# 4_Unextended_Standard_periferals.net
KiCad netlist of a schematic drawn in Altium Designer
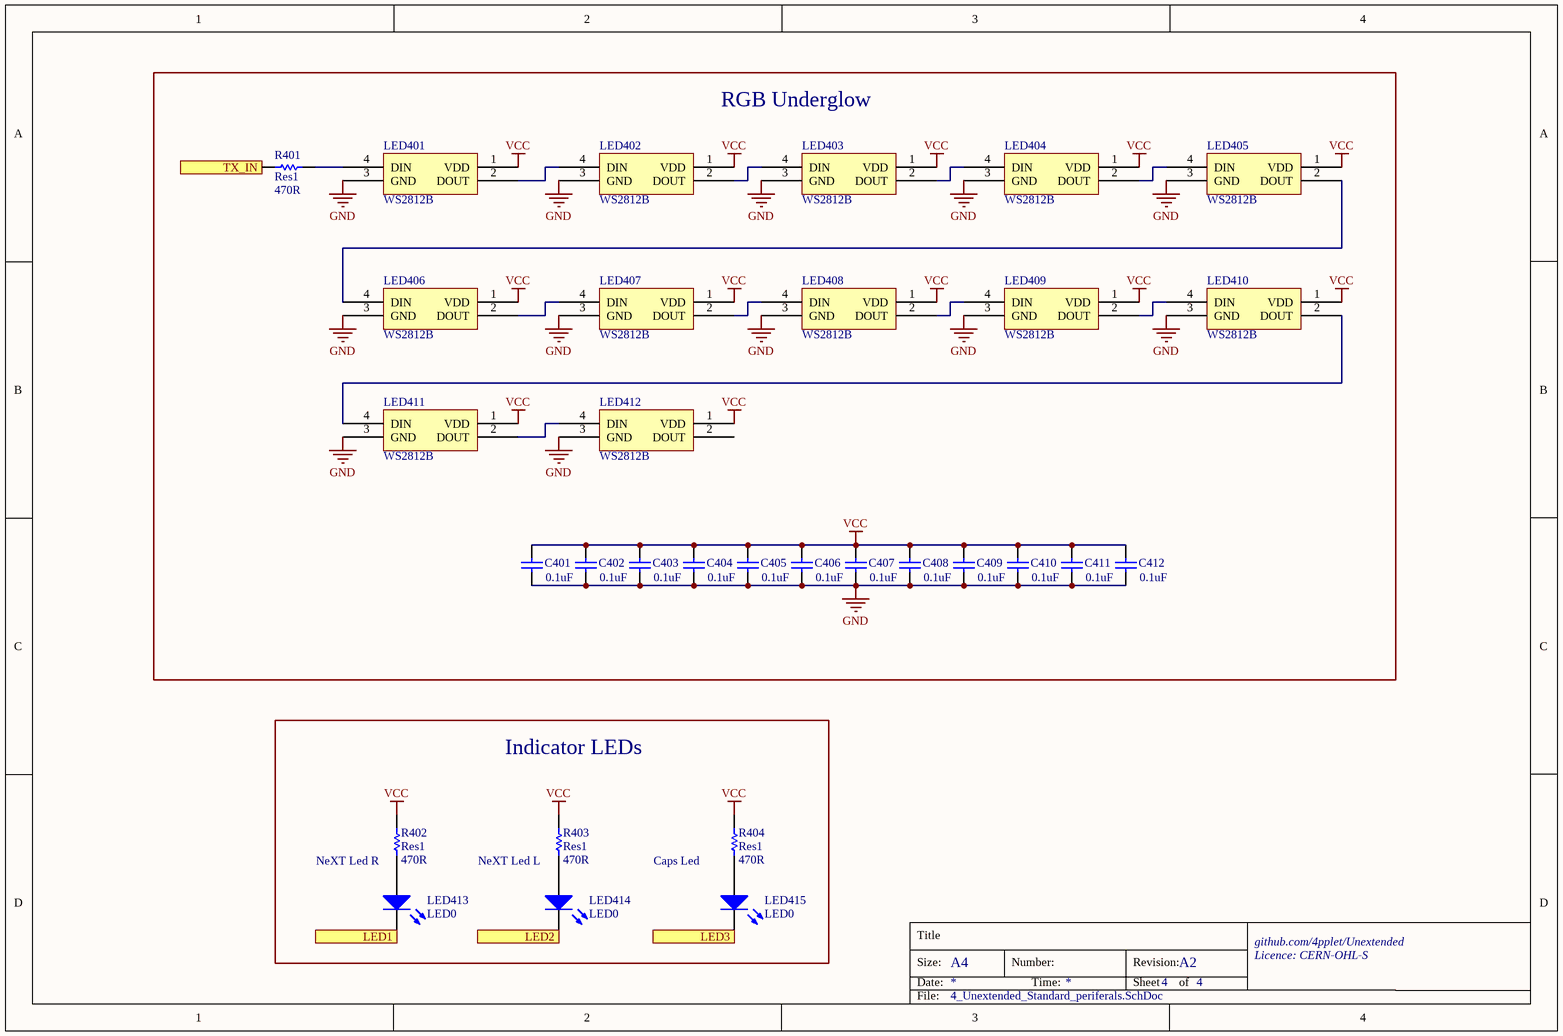
[diagram p0: 4_Unextended_Standard_periferals.SchDoc]

(export (version "E")
  (design (tool "Eeschema 10.0.6"))
  (components
    (comp (ref "C401")
      (value "0.1uF")
      (footprint "C0603[1608]")
      (description "Capacitor")
      (fields (field (name "LCSC PART #") "C14663") (field (name "MRF.PART") "CC0603KRX7R9BB104"))
      (libsource (lib "Miscellaneous Devices") (part "Cap"))
    )
    (comp (ref "C402")
      (value "0.1uF")
      (footprint "C0603[1608]")
      (description "Capacitor")
      (fields (field (name "LCSC PART #") "C14663") (field (name "MRF.PART") "CC0603KRX7R9BB104"))
      (libsource (lib "Miscellaneous Devices") (part "Cap"))
    )
    (comp (ref "C403")
      (value "0.1uF")
      (footprint "C0603[1608]")
      (description "Capacitor")
      (fields (field (name "LCSC PART #") "C14663") (field (name "MRF.PART") "CC0603KRX7R9BB104"))
      (libsource (lib "Miscellaneous Devices") (part "Cap"))
    )
    (comp (ref "C404")
      (value "0.1uF")
      (footprint "C0603[1608]")
      (description "Capacitor")
      (fields (field (name "LCSC PART #") "C14663") (field (name "MRF.PART") "CC0603KRX7R9BB104"))
      (libsource (lib "Miscellaneous Devices") (part "Cap"))
    )
    (comp (ref "C405")
      (value "0.1uF")
      (footprint "C0603[1608]")
      (description "Capacitor")
      (fields (field (name "LCSC PART #") "C14663") (field (name "MRF.PART") "CC0603KRX7R9BB104"))
      (libsource (lib "Miscellaneous Devices") (part "Cap"))
    )
    (comp (ref "C406")
      (value "0.1uF")
      (footprint "C0603[1608]")
      (description "Capacitor")
      (fields (field (name "LCSC PART #") "C14663") (field (name "MRF.PART") "CC0603KRX7R9BB104"))
      (libsource (lib "Miscellaneous Devices") (part "Cap"))
    )
    (comp (ref "C407")
      (value "0.1uF")
      (footprint "C0603[1608]")
      (description "Capacitor")
      (fields (field (name "LCSC PART #") "C14663") (field (name "MRF.PART") "CC0603KRX7R9BB104"))
      (libsource (lib "Miscellaneous Devices") (part "Cap"))
    )
    (comp (ref "C408")
      (value "0.1uF")
      (footprint "C0603[1608]")
      (description "Capacitor")
      (fields (field (name "LCSC PART #") "C14663") (field (name "MRF.PART") "CC0603KRX7R9BB104"))
      (libsource (lib "Miscellaneous Devices") (part "Cap"))
    )
    (comp (ref "C409")
      (value "0.1uF")
      (footprint "C0603[1608]")
      (description "Capacitor")
      (fields (field (name "LCSC PART #") "C14663") (field (name "MRF.PART") "CC0603KRX7R9BB104"))
      (libsource (lib "Miscellaneous Devices") (part "Cap"))
    )
    (comp (ref "C410")
      (value "0.1uF")
      (footprint "C0603[1608]")
      (description "Capacitor")
      (fields (field (name "LCSC PART #") "C14663") (field (name "MRF.PART") "CC0603KRX7R9BB104"))
      (libsource (lib "Miscellaneous Devices") (part "Cap"))
    )
    (comp (ref "C411")
      (value "0.1uF")
      (footprint "C0603[1608]")
      (description "Capacitor")
      (fields (field (name "LCSC PART #") "C14663") (field (name "MRF.PART") "CC0603KRX7R9BB104"))
      (libsource (lib "Miscellaneous Devices") (part "Cap"))
    )
    (comp (ref "C412")
      (value "0.1uF")
      (footprint "C0603[1608]")
      (description "Capacitor")
      (fields (field (name "LCSC PART #") "C14663") (field (name "MRF.PART") "CC0603KRX7R9BB104"))
      (libsource (lib "Miscellaneous Devices") (part "Cap"))
    )
    (comp (ref "LED401")
      (value "WS2812B")
      (footprint "WS2812B - 5050")
      (fields (field (name "LCSC PART #") "C2920042") (field (name "MRF.PART") "WS2812E-V5"))
      (libsource (lib "Keebs") (part "WS2812B"))
    )
    (comp (ref "LED402")
      (value "WS2812B")
      (footprint "WS2812B - 5050")
      (fields (field (name "LCSC PART #") "C2920042") (field (name "MRF.PART") "WS2812E-V5"))
      (libsource (lib "Keebs") (part "WS2812B"))
    )
    (comp (ref "LED403")
      (value "WS2812B")
      (footprint "WS2812B - 5050")
      (fields (field (name "LCSC PART #") "C2920042") (field (name "MRF.PART") "WS2812E-V5"))
      (libsource (lib "Keebs") (part "WS2812B"))
    )
    (comp (ref "LED404")
      (value "WS2812B")
      (footprint "WS2812B - 5050")
      (fields (field (name "LCSC PART #") "C2920042") (field (name "MRF.PART") "WS2812E-V5"))
      (libsource (lib "Keebs") (part "WS2812B"))
    )
    (comp (ref "LED405")
      (value "WS2812B")
      (footprint "WS2812B - 5050")
      (fields (field (name "LCSC PART #") "C2920042") (field (name "MRF.PART") "WS2812E-V5"))
      (libsource (lib "Keebs") (part "WS2812B"))
    )
    (comp (ref "LED406")
      (value "WS2812B")
      (footprint "WS2812B - 5050")
      (fields (field (name "LCSC PART #") "C2920042") (field (name "MRF.PART") "WS2812E-V5"))
      (libsource (lib "Keebs") (part "WS2812B"))
    )
    (comp (ref "LED407")
      (value "WS2812B")
      (footprint "WS2812B - 5050")
      (fields (field (name "LCSC PART #") "C2920042") (field (name "MRF.PART") "WS2812E-V5"))
      (libsource (lib "Keebs") (part "WS2812B"))
    )
    (comp (ref "LED408")
      (value "WS2812B")
      (footprint "WS2812B - 5050")
      (fields (field (name "LCSC PART #") "C2920042") (field (name "MRF.PART") "WS2812E-V5"))
      (libsource (lib "Keebs") (part "WS2812B"))
    )
    (comp (ref "LED409")
      (value "WS2812B")
      (footprint "WS2812B - 5050")
      (fields (field (name "LCSC PART #") "C2920042") (field (name "MRF.PART") "WS2812E-V5"))
      (libsource (lib "Keebs") (part "WS2812B"))
    )
    (comp (ref "LED410")
      (value "WS2812B")
      (footprint "WS2812B - 5050")
      (fields (field (name "LCSC PART #") "C2920042") (field (name "MRF.PART") "WS2812E-V5"))
      (libsource (lib "Keebs") (part "WS2812B"))
    )
    (comp (ref "LED411")
      (value "WS2812B")
      (footprint "WS2812B - 5050")
      (fields (field (name "LCSC PART #") "C2920042") (field (name "MRF.PART") "WS2812E-V5"))
      (libsource (lib "Keebs") (part "WS2812B"))
    )
    (comp (ref "LED412")
      (value "WS2812B")
      (footprint "WS2812B - 5050")
      (fields (field (name "LCSC PART #") "C2920042") (field (name "MRF.PART") "WS2812E-V5"))
      (libsource (lib "Keebs") (part "WS2812B"))
    )
    (comp (ref "LED413")
      (value "LED0")
      (footprint "SWITCH_LED - 1U")
      (description "Typical INFRARED GaAs LED")
      (libsource (lib "Miscellaneous Devices") (part "LED0"))
    )
    (comp (ref "LED414")
      (value "LED0")
      (footprint "SWITCH_LED - 1U")
      (description "Typical INFRARED GaAs LED")
      (libsource (lib "Miscellaneous Devices") (part "LED0"))
    )
    (comp (ref "LED415")
      (value "LED0")
      (footprint "SWITCH_LED - 1U")
      (description "Typical INFRARED GaAs LED")
      (libsource (lib "Miscellaneous Devices") (part "LED0"))
    )
    (comp (ref "R401")
      (value "Res1")
      (footprint "R0603[1608]")
      (description "Resistor")
      (fields
        (field (name "ALTIUM_VALUE") "470R")
        (field (name "LCSC PART #") "C23179")
        (field (name "MRF.PART") "0603WAF4700T5E")
      )
      (libsource (lib "Miscellaneous Devices") (part "Res1"))
    )
    (comp (ref "R402")
      (value "Res1")
      (footprint "R0603[1608]")
      (description "Resistor")
      (fields
        (field (name "ALTIUM_VALUE") "470R")
        (field (name "LCSC PART #") "C23179")
        (field (name "MRF.PART") "0603WAF4700T5E")
      )
      (libsource (lib "Miscellaneous Devices") (part "Res1"))
    )
    (comp (ref "R403")
      (value "Res1")
      (footprint "R0603[1608]")
      (description "Resistor")
      (fields
        (field (name "ALTIUM_VALUE") "470R")
        (field (name "LCSC PART #") "C23179")
        (field (name "MRF.PART") "0603WAF4700T5E")
      )
      (libsource (lib "Miscellaneous Devices") (part "Res1"))
    )
    (comp (ref "R404")
      (value "Res1")
      (footprint "R0603[1608]")
      (description "Resistor")
      (fields
        (field (name "ALTIUM_VALUE") "470R")
        (field (name "LCSC PART #") "C23179")
        (field (name "MRF.PART") "0603WAF4700T5E")
      )
      (libsource (lib "Miscellaneous Devices") (part "Res1"))
    )
  )
  (nets
    (net (code "1") (name "/LED1") (class "Default")
      (node (ref "LED413") (pin "2") (pinfunction "K_2") (pintype "passive"))
    )
    (net (code "2") (name "/LED2") (class "Default")
      (node (ref "LED414") (pin "2") (pinfunction "K_2") (pintype "passive"))
    )
    (net (code "3") (name "/LED3") (class "Default")
      (node (ref "LED415") (pin "2") (pinfunction "K_2") (pintype "passive"))
    )
    (net (code "4") (name "/TX_IN") (class "Default")
      (node (ref "R401") (pin "1") (pinfunction "1_1") (pintype "passive"))
    )
    (net (code "5") (name "GND") (class "Default")
      (node (ref "C401") (pin "1") (pinfunction "1_1") (pintype "passive"))
      (node (ref "C402") (pin "1") (pinfunction "1_1") (pintype "passive"))
      (node (ref "C403") (pin "1") (pinfunction "1_1") (pintype "passive"))
      (node (ref "C404") (pin "1") (pinfunction "1_1") (pintype "passive"))
      (node (ref "C405") (pin "1") (pinfunction "1_1") (pintype "passive"))
      (node (ref "C406") (pin "1") (pinfunction "1_1") (pintype "passive"))
      (node (ref "C407") (pin "1") (pinfunction "1_1") (pintype "passive"))
      (node (ref "C408") (pin "1") (pinfunction "1_1") (pintype "passive"))
      (node (ref "C409") (pin "1") (pinfunction "1_1") (pintype "passive"))
      (node (ref "C410") (pin "1") (pinfunction "1_1") (pintype "passive"))
      (node (ref "C411") (pin "1") (pinfunction "1_1") (pintype "passive"))
      (node (ref "C412") (pin "1") (pinfunction "1_1") (pintype "passive"))
      (node (ref "LED401") (pin "3") (pinfunction "GND_3") (pintype "passive"))
      (node (ref "LED402") (pin "3") (pinfunction "GND_3") (pintype "passive"))
      (node (ref "LED403") (pin "3") (pinfunction "GND_3") (pintype "passive"))
      (node (ref "LED404") (pin "3") (pinfunction "GND_3") (pintype "passive"))
      (node (ref "LED405") (pin "3") (pinfunction "GND_3") (pintype "passive"))
      (node (ref "LED406") (pin "3") (pinfunction "GND_3") (pintype "passive"))
      (node (ref "LED407") (pin "3") (pinfunction "GND_3") (pintype "passive"))
      (node (ref "LED408") (pin "3") (pinfunction "GND_3") (pintype "passive"))
      (node (ref "LED409") (pin "3") (pinfunction "GND_3") (pintype "passive"))
      (node (ref "LED410") (pin "3") (pinfunction "GND_3") (pintype "passive"))
      (node (ref "LED411") (pin "3") (pinfunction "GND_3") (pintype "passive"))
      (node (ref "LED412") (pin "3") (pinfunction "GND_3") (pintype "passive"))
    )
    (net (code "6") (name "Net-(LED401-DIN)") (class "Default")
      (node (ref "LED401") (pin "4") (pinfunction "DIN_4") (pintype "passive"))
      (node (ref "R401") (pin "2") (pinfunction "2_2") (pintype "passive"))
    )
    (net (code "7") (name "Net-(LED401-DOUT)") (class "Default")
      (node (ref "LED401") (pin "2") (pinfunction "DOUT_2") (pintype "passive"))
      (node (ref "LED402") (pin "4") (pinfunction "DIN_4") (pintype "passive"))
    )
    (net (code "8") (name "Net-(LED402-DOUT)") (class "Default")
      (node (ref "LED402") (pin "2") (pinfunction "DOUT_2") (pintype "passive"))
      (node (ref "LED403") (pin "4") (pinfunction "DIN_4") (pintype "passive"))
    )
    (net (code "9") (name "Net-(LED403-DOUT)") (class "Default")
      (node (ref "LED403") (pin "2") (pinfunction "DOUT_2") (pintype "passive"))
      (node (ref "LED404") (pin "4") (pinfunction "DIN_4") (pintype "passive"))
    )
    (net (code "10") (name "Net-(LED404-DOUT)") (class "Default")
      (node (ref "LED404") (pin "2") (pinfunction "DOUT_2") (pintype "passive"))
      (node (ref "LED405") (pin "4") (pinfunction "DIN_4") (pintype "passive"))
    )
    (net (code "11") (name "Net-(LED405-DOUT)") (class "Default")
      (node (ref "LED405") (pin "2") (pinfunction "DOUT_2") (pintype "passive"))
      (node (ref "LED406") (pin "4") (pinfunction "DIN_4") (pintype "passive"))
    )
    (net (code "12") (name "Net-(LED406-DOUT)") (class "Default")
      (node (ref "LED406") (pin "2") (pinfunction "DOUT_2") (pintype "passive"))
      (node (ref "LED407") (pin "4") (pinfunction "DIN_4") (pintype "passive"))
    )
    (net (code "13") (name "Net-(LED407-DOUT)") (class "Default")
      (node (ref "LED407") (pin "2") (pinfunction "DOUT_2") (pintype "passive"))
      (node (ref "LED408") (pin "4") (pinfunction "DIN_4") (pintype "passive"))
    )
    (net (code "14") (name "Net-(LED408-DOUT)") (class "Default")
      (node (ref "LED408") (pin "2") (pinfunction "DOUT_2") (pintype "passive"))
      (node (ref "LED409") (pin "4") (pinfunction "DIN_4") (pintype "passive"))
    )
    (net (code "15") (name "Net-(LED409-DOUT)") (class "Default")
      (node (ref "LED409") (pin "2") (pinfunction "DOUT_2") (pintype "passive"))
      (node (ref "LED410") (pin "4") (pinfunction "DIN_4") (pintype "passive"))
    )
    (net (code "16") (name "Net-(LED410-DOUT)") (class "Default")
      (node (ref "LED410") (pin "2") (pinfunction "DOUT_2") (pintype "passive"))
      (node (ref "LED411") (pin "4") (pinfunction "DIN_4") (pintype "passive"))
    )
    (net (code "17") (name "Net-(LED411-DOUT)") (class "Default")
      (node (ref "LED411") (pin "2") (pinfunction "DOUT_2") (pintype "passive"))
      (node (ref "LED412") (pin "4") (pinfunction "DIN_4") (pintype "passive"))
    )
    (net (code "18") (name "Net-(LED413-A)") (class "Default")
      (node (ref "LED413") (pin "1") (pinfunction "A_1") (pintype "passive"))
      (node (ref "R402") (pin "1") (pinfunction "1_1") (pintype "passive"))
    )
    (net (code "19") (name "Net-(LED414-A)") (class "Default")
      (node (ref "LED414") (pin "1") (pinfunction "A_1") (pintype "passive"))
      (node (ref "R403") (pin "1") (pinfunction "1_1") (pintype "passive"))
    )
    (net (code "20") (name "Net-(LED415-A)") (class "Default")
      (node (ref "LED415") (pin "1") (pinfunction "A_1") (pintype "passive"))
      (node (ref "R404") (pin "1") (pinfunction "1_1") (pintype "passive"))
    )
    (net (code "21") (name "VCC") (class "Default")
      (node (ref "C401") (pin "2") (pinfunction "2_2") (pintype "passive"))
      (node (ref "C402") (pin "2") (pinfunction "2_2") (pintype "passive"))
      (node (ref "C403") (pin "2") (pinfunction "2_2") (pintype "passive"))
      (node (ref "C404") (pin "2") (pinfunction "2_2") (pintype "passive"))
      (node (ref "C405") (pin "2") (pinfunction "2_2") (pintype "passive"))
      (node (ref "C406") (pin "2") (pinfunction "2_2") (pintype "passive"))
      (node (ref "C407") (pin "2") (pinfunction "2_2") (pintype "passive"))
      (node (ref "C408") (pin "2") (pinfunction "2_2") (pintype "passive"))
      (node (ref "C409") (pin "2") (pinfunction "2_2") (pintype "passive"))
      (node (ref "C410") (pin "2") (pinfunction "2_2") (pintype "passive"))
      (node (ref "C411") (pin "2") (pinfunction "2_2") (pintype "passive"))
      (node (ref "C412") (pin "2") (pinfunction "2_2") (pintype "passive"))
      (node (ref "LED401") (pin "1") (pinfunction "VDD_1") (pintype "passive"))
      (node (ref "LED402") (pin "1") (pinfunction "VDD_1") (pintype "passive"))
      (node (ref "LED403") (pin "1") (pinfunction "VDD_1") (pintype "passive"))
      (node (ref "LED404") (pin "1") (pinfunction "VDD_1") (pintype "passive"))
      (node (ref "LED405") (pin "1") (pinfunction "VDD_1") (pintype "passive"))
      (node (ref "LED406") (pin "1") (pinfunction "VDD_1") (pintype "passive"))
      (node (ref "LED407") (pin "1") (pinfunction "VDD_1") (pintype "passive"))
      (node (ref "LED408") (pin "1") (pinfunction "VDD_1") (pintype "passive"))
      (node (ref "LED409") (pin "1") (pinfunction "VDD_1") (pintype "passive"))
      (node (ref "LED410") (pin "1") (pinfunction "VDD_1") (pintype "passive"))
      (node (ref "LED411") (pin "1") (pinfunction "VDD_1") (pintype "passive"))
      (node (ref "LED412") (pin "1") (pinfunction "VDD_1") (pintype "passive"))
      (node (ref "R402") (pin "2") (pinfunction "2_2") (pintype "passive"))
      (node (ref "R403") (pin "2") (pinfunction "2_2") (pintype "passive"))
      (node (ref "R404") (pin "2") (pinfunction "2_2") (pintype "passive"))
    )
    (net (code "22") (name "unconnected-(LED412-DOUT-Pad2)") (class "Default")
      (node (ref "LED412") (pin "2") (pinfunction "DOUT_2") (pintype "passive"))
    )
  )
)
